# G100_PTC_RS232_201806.net
KiCad netlist of a schematic drawn in Altium Designer
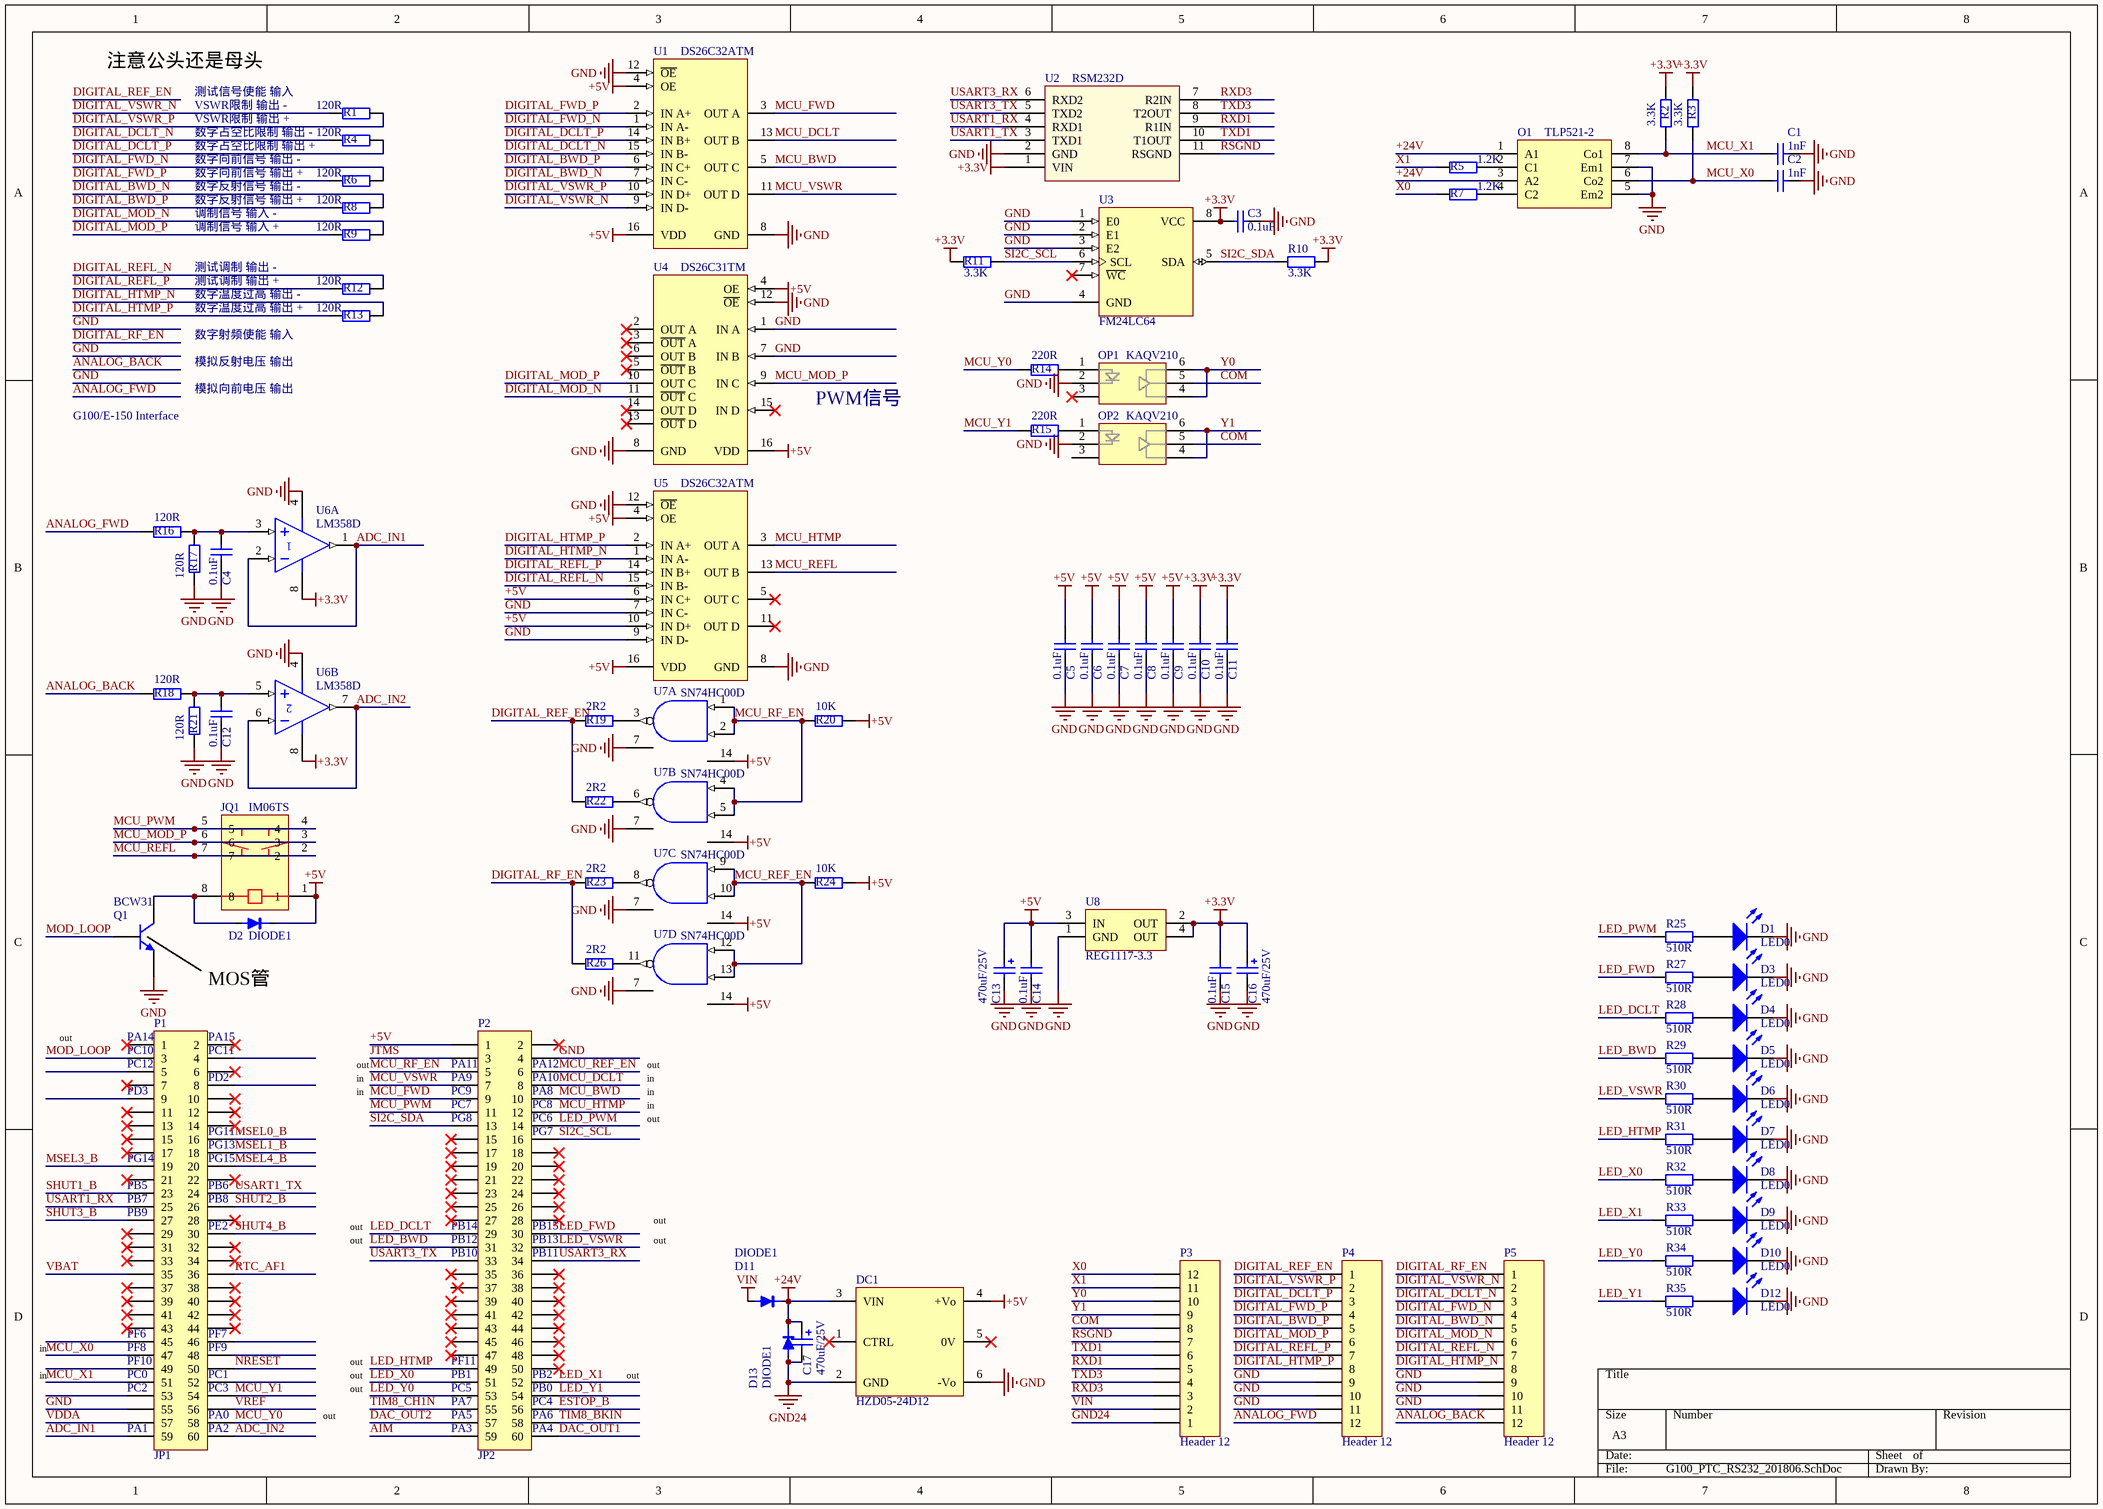
[diagram p0: G100_PTC_RS232_201806.SchDoc]

(export (version "E")
  (design (tool "Eeschema 10.0.6"))
  (components
    (comp (ref "C1")
      (value "1nF")
      (footprint "0805C")
      (description "Capacitor")
      (fields (field (name "PUBLISHER") "Altium Limited"))
      (libsource (lib "Miscellaneous Devices") (part "Cap"))
    )
    (comp (ref "C2")
      (value "1nF")
      (footprint "0805C")
      (description "Capacitor")
      (fields (field (name "PUBLISHER") "Altium Limited"))
      (libsource (lib "Miscellaneous Devices") (part "Cap"))
    )
    (comp (ref "C3")
      (value "0.1uF")
      (footprint "0805C")
      (description "Capacitor")
      (fields (field (name "PUBLISHER") "Altium Limited"))
      (libsource (lib "Miscellaneous Devices") (part "Cap"))
    )
    (comp (ref "C4")
      (value "0.1uF")
      (footprint "0805C")
      (description "Capacitor")
      (fields (field (name "PUBLISHER") "Altium Limited"))
      (libsource (lib "Miscellaneous Devices") (part "Cap"))
    )
    (comp (ref "C5")
      (value "0.1uF")
      (footprint "0805C")
      (description "Capacitor")
      (fields (field (name "PUBLISHER") "Altium Limited"))
      (libsource (lib "Miscellaneous Devices") (part "Cap"))
    )
    (comp (ref "C6")
      (value "0.1uF")
      (footprint "0805C")
      (description "Capacitor")
      (fields (field (name "PUBLISHER") "Altium Limited"))
      (libsource (lib "Miscellaneous Devices") (part "Cap"))
    )
    (comp (ref "C7")
      (value "0.1uF")
      (footprint "0805C")
      (description "Capacitor")
      (fields (field (name "PUBLISHER") "Altium Limited"))
      (libsource (lib "Miscellaneous Devices") (part "Cap"))
    )
    (comp (ref "C8")
      (value "0.1uF")
      (footprint "0805C")
      (description "Capacitor")
      (fields (field (name "PUBLISHER") "Altium Limited"))
      (libsource (lib "Miscellaneous Devices") (part "Cap"))
    )
    (comp (ref "C9")
      (value "0.1uF")
      (footprint "0805C")
      (description "Capacitor")
      (fields (field (name "PUBLISHER") "Altium Limited"))
      (libsource (lib "Miscellaneous Devices") (part "Cap"))
    )
    (comp (ref "C10")
      (value "0.1uF")
      (footprint "0805C")
      (description "Capacitor")
      (fields (field (name "PUBLISHER") "Altium Limited"))
      (libsource (lib "Miscellaneous Devices") (part "Cap"))
    )
    (comp (ref "C11")
      (value "0.1uF")
      (footprint "0805C")
      (description "Capacitor")
      (fields (field (name "PUBLISHER") "Altium Limited"))
      (libsource (lib "Miscellaneous Devices") (part "Cap"))
    )
    (comp (ref "C12")
      (value "0.1uF")
      (footprint "0805C")
      (description "Capacitor")
      (fields (field (name "PUBLISHER") "Altium Limited"))
      (libsource (lib "Miscellaneous Devices") (part "Cap"))
    )
    (comp (ref "C13")
      (value "470uF/25V")
      (footprint "RB3.5-8")
      (description "Polarized Capacitor (Axial)")
      (fields (field (name "PUBLISHER") "Altium Limited"))
      (libsource (lib "Miscellaneous Devices") (part "Cap Pol2"))
    )
    (comp (ref "C14")
      (value "0.1uF")
      (footprint "0805C")
      (description "Capacitor")
      (fields (field (name "PUBLISHER") "Altium Limited"))
      (libsource (lib "Miscellaneous Devices") (part "Cap"))
    )
    (comp (ref "C15")
      (value "0.1uF")
      (footprint "0805C")
      (description "Capacitor")
      (fields (field (name "PUBLISHER") "Altium Limited"))
      (libsource (lib "Miscellaneous Devices") (part "Cap"))
    )
    (comp (ref "C16")
      (value "470uF/25V")
      (footprint "RB3.5-8")
      (description "Polarized Capacitor (Axial)")
      (fields (field (name "PUBLISHER") "Altium Limited"))
      (libsource (lib "Miscellaneous Devices") (part "Cap Pol2"))
    )
    (comp (ref "C17")
      (value "470uF/25V")
      (footprint "RB3.5-8")
      (description "Polarized Capacitor (Axial)")
      (fields (field (name "PUBLISHER") "Altium Limited"))
      (libsource (lib "Miscellaneous Devices") (part "Cap Pol2"))
    )
    (comp (ref "D1")
      (value "LED0")
      (footprint "LEDLight")
      (description "Typical INFRARED GaAs LED")
      (fields (field (name "PUBLISHER") "Altium Limited"))
      (libsource (lib "Miscellaneous Devices") (part "LED0"))
    )
    (comp (ref "D2") (value "DIODE1") (footprint "SOD123") (libsource (lib "常用元件库") (part "DIODE1")))
    (comp (ref "D3")
      (value "LED0")
      (footprint "LEDLight")
      (description "Typical INFRARED GaAs LED")
      (fields (field (name "PUBLISHER") "Altium Limited"))
      (libsource (lib "Miscellaneous Devices") (part "LED0"))
    )
    (comp (ref "D4")
      (value "LED0")
      (footprint "LEDLight")
      (description "Typical INFRARED GaAs LED")
      (fields (field (name "PUBLISHER") "Altium Limited"))
      (libsource (lib "Miscellaneous Devices") (part "LED0"))
    )
    (comp (ref "D5")
      (value "LED0")
      (footprint "LEDLight")
      (description "Typical INFRARED GaAs LED")
      (fields (field (name "PUBLISHER") "Altium Limited"))
      (libsource (lib "Miscellaneous Devices") (part "LED0"))
    )
    (comp (ref "D6")
      (value "LED0")
      (footprint "LEDLight")
      (description "Typical INFRARED GaAs LED")
      (fields (field (name "PUBLISHER") "Altium Limited"))
      (libsource (lib "Miscellaneous Devices") (part "LED0"))
    )
    (comp (ref "D7")
      (value "LED0")
      (footprint "LEDLight")
      (description "Typical INFRARED GaAs LED")
      (fields (field (name "PUBLISHER") "Altium Limited"))
      (libsource (lib "Miscellaneous Devices") (part "LED0"))
    )
    (comp (ref "D8")
      (value "LED0")
      (footprint "LEDLight")
      (description "Typical INFRARED GaAs LED")
      (fields (field (name "PUBLISHER") "Altium Limited"))
      (libsource (lib "Miscellaneous Devices") (part "LED0"))
    )
    (comp (ref "D9")
      (value "LED0")
      (footprint "LEDLight")
      (description "Typical INFRARED GaAs LED")
      (fields (field (name "PUBLISHER") "Altium Limited"))
      (libsource (lib "Miscellaneous Devices") (part "LED0"))
    )
    (comp (ref "D10")
      (value "LED0")
      (footprint "LEDLight")
      (description "Typical INFRARED GaAs LED")
      (fields (field (name "PUBLISHER") "Altium Limited"))
      (libsource (lib "Miscellaneous Devices") (part "LED0"))
    )
    (comp (ref "D11") (value "DIODE1") (footprint "DIODE-DO56") (libsource (lib "常用元件库") (part "DIODE1")))
    (comp (ref "D12")
      (value "LED0")
      (footprint "LEDLight")
      (description "Typical INFRARED GaAs LED")
      (fields (field (name "PUBLISHER") "Altium Limited"))
      (libsource (lib "Miscellaneous Devices") (part "LED0"))
    )
    (comp (ref "D13") (value "DIODE1") (footprint "DIODE-DO56") (libsource (lib "常用元件库") (part "DIODE1")))
    (comp (ref "DC1")
      (value "HZD05-24D12")
      (footprint "HZ03V2")
      (libsource (lib "常用原理图库") (part "HZD05-24D12"))
    )
    (comp (ref "JQ1") (value "IM06TS") (footprint "IM06TS") (libsource (lib "常用原理图库") (part "IM06TS")))
    (comp (ref "O1")
      (value "TLP521-2")
      (footprint "DIP-8")
      (description "Photocoupler")
      (libsource (lib "常用原理图库") (part "TLP521-2"))
    )
    (comp (ref "OP1") (value "KAQV210") (footprint "DIP-6") (libsource (lib "常用原理图库") (part "KAQV210")))
    (comp (ref "OP2") (value "KAQV210") (footprint "DIP-6") (libsource (lib "常用原理图库") (part "KAQV210")))
    (comp (ref "P1")
      (value "JP1")
      (footprint "HDR2X30")
      (description "Header, 30-Pin, Dual row")
      (fields (field (name "PUBLISHER") "Altium Limited"))
      (libsource (lib "Miscellaneous Connectors") (part "Header 30X2"))
    )
    (comp (ref "P2")
      (value "JP2")
      (footprint "HDR2X30")
      (description "Header, 30-Pin, Dual row")
      (fields (field (name "PUBLISHER") "Altium Limited"))
      (libsource (lib "Miscellaneous Connectors") (part "Header 30X2"))
    )
    (comp (ref "P3")
      (value "Header 12")
      (footprint "15EDGVM-3.5-12P-14")
      (description "Header, 12-Pin")
      (fields (field (name "PUBLISHER") "Altium Limited"))
      (libsource (lib "") (part "Header 12_1"))
    )
    (comp (ref "P4")
      (value "Header 12")
      (footprint "15EDGVM-3.5-12P-14")
      (description "Header, 12-Pin")
      (fields (field (name "PUBLISHER") "Altium Limited"))
      (libsource (lib "Miscellaneous Connectors") (part "Header 12"))
    )
    (comp (ref "P5")
      (value "Header 12")
      (footprint "15EDGVM-3.5-12P-14")
      (description "Header, 12-Pin")
      (fields (field (name "PUBLISHER") "Altium Limited"))
      (libsource (lib "Miscellaneous Connectors") (part "Header 12"))
    )
    (comp (ref "Q1")
      (value "BCW31")
      (footprint "SOT-23A")
      (description "NPN Epitaxial Silicon Transistor")
      (fields (field (name "PUBLISHER") "Altium Limited"))
      (libsource (lib "FSC Discrete BJT") (part "BCW31"))
    )
    (comp (ref "R1")
      (value "120R")
      (footprint "0805C")
      (description "Resistor")
      (fields (field (name "PUBLISHER") "Altium Limited"))
      (libsource (lib "Miscellaneous Devices") (part "Res2"))
    )
    (comp (ref "R2")
      (value "3.3K")
      (footprint "0805C")
      (description "Resistor")
      (fields (field (name "PUBLISHER") "Altium Limited"))
      (libsource (lib "") (part "Res2_3"))
    )
    (comp (ref "R3")
      (value "3.3K")
      (footprint "0805C")
      (description "Resistor")
      (fields (field (name "PUBLISHER") "Altium Limited"))
      (libsource (lib "") (part "Res2_3"))
    )
    (comp (ref "R4")
      (value "120R")
      (footprint "0805C")
      (description "Resistor")
      (fields (field (name "PUBLISHER") "Altium Limited"))
      (libsource (lib "Miscellaneous Devices") (part "Res2"))
    )
    (comp (ref "R5")
      (value "1.2K")
      (footprint "6332[2512]")
      (description "Resistor")
      (fields (field (name "PUBLISHER") "Altium Limited"))
      (libsource (lib "") (part "Res2_1"))
    )
    (comp (ref "R6")
      (value "120R")
      (footprint "0805C")
      (description "Resistor")
      (fields (field (name "PUBLISHER") "Altium Limited"))
      (libsource (lib "Miscellaneous Devices") (part "Res2"))
    )
    (comp (ref "R7")
      (value "1.2K")
      (footprint "6332[2512]")
      (description "Resistor")
      (fields (field (name "PUBLISHER") "Altium Limited"))
      (libsource (lib "") (part "Res2_1"))
    )
    (comp (ref "R8")
      (value "120R")
      (footprint "0805C")
      (description "Resistor")
      (fields (field (name "PUBLISHER") "Altium Limited"))
      (libsource (lib "Miscellaneous Devices") (part "Res2"))
    )
    (comp (ref "R9")
      (value "120R")
      (footprint "0805C")
      (description "Resistor")
      (fields (field (name "PUBLISHER") "Altium Limited"))
      (libsource (lib "Miscellaneous Devices") (part "Res2"))
    )
    (comp (ref "R10")
      (value "3.3K")
      (footprint "0805C")
      (description "Resistor")
      (fields (field (name "PUBLISHER") "Altium Limited"))
      (libsource (lib "") (part "Res2_1"))
    )
    (comp (ref "R11")
      (value "3.3K")
      (footprint "0805C")
      (description "Resistor")
      (fields (field (name "PUBLISHER") "Altium Limited"))
      (libsource (lib "Miscellaneous Devices") (part "Res2"))
    )
    (comp (ref "R12")
      (value "120R")
      (footprint "0805C")
      (description "Resistor")
      (fields (field (name "PUBLISHER") "Altium Limited"))
      (libsource (lib "Miscellaneous Devices") (part "Res2"))
    )
    (comp (ref "R13")
      (value "120R")
      (footprint "0805C")
      (description "Resistor")
      (fields (field (name "PUBLISHER") "Altium Limited"))
      (libsource (lib "Miscellaneous Devices") (part "Res2"))
    )
    (comp (ref "R14")
      (value "220R")
      (footprint "0805C")
      (description "Resistor")
      (fields (field (name "PUBLISHER") "Altium Limited"))
      (libsource (lib "Miscellaneous Devices") (part "Res2"))
    )
    (comp (ref "R15")
      (value "220R")
      (footprint "0805C")
      (description "Resistor")
      (fields (field (name "PUBLISHER") "Altium Limited"))
      (libsource (lib "Miscellaneous Devices") (part "Res2"))
    )
    (comp (ref "R16")
      (value "120R")
      (footprint "0805C")
      (description "Resistor")
      (fields (field (name "PUBLISHER") "Altium Limited"))
      (libsource (lib "Miscellaneous Devices") (part "Res2"))
    )
    (comp (ref "R17")
      (value "120R")
      (footprint "0805C")
      (description "Resistor")
      (fields (field (name "PUBLISHER") "Altium Limited"))
      (libsource (lib "") (part "Res2_2"))
    )
    (comp (ref "R18")
      (value "120R")
      (footprint "0805C")
      (description "Resistor")
      (fields (field (name "PUBLISHER") "Altium Limited"))
      (libsource (lib "Miscellaneous Devices") (part "Res2"))
    )
    (comp (ref "R19")
      (value "2R2")
      (footprint "0805C")
      (description "Resistor")
      (fields (field (name "PUBLISHER") "Altium Limited"))
      (libsource (lib "Miscellaneous Devices") (part "Res2"))
    )
    (comp (ref "R20")
      (value "10K")
      (footprint "0805C")
      (description "Resistor")
      (fields (field (name "PUBLISHER") "Altium Limited"))
      (libsource (lib "Miscellaneous Devices") (part "Res2"))
    )
    (comp (ref "R21")
      (value "120R")
      (footprint "0805C")
      (description "Resistor")
      (fields (field (name "PUBLISHER") "Altium Limited"))
      (libsource (lib "") (part "Res2_2"))
    )
    (comp (ref "R22")
      (value "2R2")
      (footprint "0805C")
      (description "Resistor")
      (fields (field (name "PUBLISHER") "Altium Limited"))
      (libsource (lib "Miscellaneous Devices") (part "Res2"))
    )
    (comp (ref "R23")
      (value "2R2")
      (footprint "0805C")
      (description "Resistor")
      (fields (field (name "PUBLISHER") "Altium Limited"))
      (libsource (lib "Miscellaneous Devices") (part "Res2"))
    )
    (comp (ref "R24")
      (value "10K")
      (footprint "0805C")
      (description "Resistor")
      (fields (field (name "PUBLISHER") "Altium Limited"))
      (libsource (lib "Miscellaneous Devices") (part "Res2"))
    )
    (comp (ref "R25")
      (value "510R")
      (footprint "0805C")
      (description "Resistor")
      (fields (field (name "PUBLISHER") "Altium Limited"))
      (libsource (lib "") (part "Res2_1"))
    )
    (comp (ref "R26")
      (value "2R2")
      (footprint "0805C")
      (description "Resistor")
      (fields (field (name "PUBLISHER") "Altium Limited"))
      (libsource (lib "Miscellaneous Devices") (part "Res2"))
    )
    (comp (ref "R27")
      (value "510R")
      (footprint "0805C")
      (description "Resistor")
      (fields (field (name "PUBLISHER") "Altium Limited"))
      (libsource (lib "") (part "Res2_1"))
    )
    (comp (ref "R28")
      (value "510R")
      (footprint "0805C")
      (description "Resistor")
      (fields (field (name "PUBLISHER") "Altium Limited"))
      (libsource (lib "") (part "Res2_1"))
    )
    (comp (ref "R29")
      (value "510R")
      (footprint "0805C")
      (description "Resistor")
      (fields (field (name "PUBLISHER") "Altium Limited"))
      (libsource (lib "") (part "Res2_1"))
    )
    (comp (ref "R30")
      (value "510R")
      (footprint "0805C")
      (description "Resistor")
      (fields (field (name "PUBLISHER") "Altium Limited"))
      (libsource (lib "") (part "Res2_1"))
    )
    (comp (ref "R31")
      (value "510R")
      (footprint "0805C")
      (description "Resistor")
      (fields (field (name "PUBLISHER") "Altium Limited"))
      (libsource (lib "") (part "Res2_1"))
    )
    (comp (ref "R32")
      (value "510R")
      (footprint "0805C")
      (description "Resistor")
      (fields (field (name "PUBLISHER") "Altium Limited"))
      (libsource (lib "") (part "Res2_1"))
    )
    (comp (ref "R33")
      (value "510R")
      (footprint "0805C")
      (description "Resistor")
      (fields (field (name "PUBLISHER") "Altium Limited"))
      (libsource (lib "") (part "Res2_1"))
    )
    (comp (ref "R34")
      (value "510R")
      (footprint "0805C")
      (description "Resistor")
      (fields (field (name "PUBLISHER") "Altium Limited"))
      (libsource (lib "") (part "Res2_1"))
    )
    (comp (ref "R35")
      (value "510R")
      (footprint "0805C")
      (description "Resistor")
      (fields (field (name "PUBLISHER") "Altium Limited"))
      (libsource (lib "") (part "Res2_1"))
    )
    (comp (ref "U1")
      (value "DS26C32ATM")
      (footprint "M16A_L")
      (description "CMOS Quad Differential Line Receiver")
      (fields
        (field (name "MANUFACTURER") "National Semiconductor")
        (field (name "DIGIKEYPARTNUMBER") "DS26C32ATM-ND")
        (field (name "PUBLISHER") "Altium Limited")
      )
      (libsource (lib "NSC Interface") (part "DS26C32ATM"))
    )
    (comp (ref "U2")
      (value "RSM232D")
      (footprint "CTM-8251D")
      (description "双路隔离RS-232收发器")
      (libsource (lib "常用原理图库") (part "RSM232D"))
    )
    (comp (ref "U3")
      (value "FM24LC64")
      (footprint "SOP8_L")
      (description "64 Kbit Serial I²C Bus EEPROM")
      (fields (field (name "PUBLISHER") "Altium Limited"))
      (libsource (lib "ST Memory EEPROM Serial") (part "M24C64MN3"))
    )
    (comp (ref "U4")
      (value "DS26C31TM")
      (footprint "M16A_L")
      (description "CMOS Quad Tri-State Differential Line Driver")
      (fields
        (field (name "MANUFACTURER") "National Semiconductor")
        (field (name "DIGIKEYPARTNUMBER") "DS26C31TM-ND")
        (field (name "PUBLISHER") "Altium Limited")
      )
      (libsource (lib "NSC Interface") (part "DS26C31TM"))
    )
    (comp (ref "U5")
      (value "DS26C32ATM")
      (footprint "M16A_L")
      (description "CMOS Quad Differential Line Receiver")
      (fields
        (field (name "MANUFACTURER") "National Semiconductor")
        (field (name "DIGIKEYPARTNUMBER") "DS26C32ATM-ND")
        (field (name "PUBLISHER") "Altium Limited")
      )
      (libsource (lib "NSC Interface") (part "DS26C32ATM"))
    )
    (comp (ref "U6")
      (value "LM358D")
      (footprint "751-02_N")
      (description "Dual Low-Power Operational Amplifier")
      (fields (field (name "PUBLISHER") "Altium Limited"))
      (libsource (lib "Motorola Amplifier Operational Amplifier") (part "LM358D"))
    )
    (comp (ref "U7")
      (value "SN74HC00D")
      (footprint "D014_N")
      (description "Quadruple 2-Input Positive-NAND Gate")
      (fields (field (name "PUBLISHER") "Altium Limited"))
      (libsource (lib "TI Logic Gate 2") (part "SN74HC00D"))
    )
    (comp (ref "U8")
      (value "REG1117-3.3")
      (footprint "ZZ311")
      (description "800mA and 1A Low Dropout Positive Regulator 2.85V, 3.3V, 5V, and Adjustable")
      (fields (field (name "PUBLISHER") "Altium Limited"))
      (libsource (lib "BB Power Mgt Voltage Regulator") (part "REG1117-3.3"))
    )
  )
  (nets
    (net (code "1") (name "+3.3V") (class "Default")
      (node (ref "C10") (pin "2") (pinfunction "2_2") (pintype "passive"))
      (node (ref "C11") (pin "2") (pinfunction "2_2") (pintype "passive"))
      (node (ref "C15") (pin "2") (pinfunction "2_2") (pintype "passive"))
      (node (ref "C16") (pin "1") (pinfunction "1_1") (pintype "passive"))
      (node (ref "C3") (pin "2") (pinfunction "2_2") (pintype "passive"))
      (node (ref "R10") (pin "2") (pinfunction "2_2") (pintype "passive"))
      (node (ref "R11") (pin "2") (pinfunction "2_2") (pintype "passive"))
      (node (ref "R2") (pin "2") (pinfunction "2_2") (pintype "passive"))
      (node (ref "R3") (pin "2") (pinfunction "2_2") (pintype "passive"))
      (node (ref "U2") (pin "1") (pinfunction "VIN_1") (pintype "passive"))
      (node (ref "U3") (pin "8") (pinfunction "VCC_8") (pintype "power_in"))
      (node (ref "U6") (pin "8") (pinfunction "V+_8") (pintype "power_in"))
      (node (ref "U8") (pin "2") (pinfunction "OUT_2") (pintype "power_in"))
      (node (ref "U8") (pin "4") (pinfunction "OUT_4") (pintype "power_in"))
    )
    (net (code "2") (name "+5V") (class "Default")
      (node (ref "C13") (pin "1") (pinfunction "1_1") (pintype "passive"))
      (node (ref "C14") (pin "2") (pinfunction "2_2") (pintype "passive"))
      (node (ref "C5") (pin "2") (pinfunction "2_2") (pintype "passive"))
      (node (ref "C6") (pin "2") (pinfunction "2_2") (pintype "passive"))
      (node (ref "C7") (pin "2") (pinfunction "2_2") (pintype "passive"))
      (node (ref "C8") (pin "2") (pinfunction "2_2") (pintype "passive"))
      (node (ref "C9") (pin "2") (pinfunction "2_2") (pintype "passive"))
      (node (ref "D2") (pin "2") (pinfunction "K_2") (pintype "passive"))
      (node (ref "DC1") (pin "4") (pinfunction "+Vo_4") (pintype "passive"))
      (node (ref "JQ1") (pin "1") (pinfunction "1_1") (pintype "passive"))
      (node (ref "P2") (pin "1") (pinfunction "1_1") (pintype "passive"))
      (node (ref "R20") (pin "1") (pinfunction "1_1") (pintype "passive"))
      (node (ref "R24") (pin "1") (pinfunction "1_1") (pintype "passive"))
      (node (ref "U1") (pin "16") (pinfunction "VDD_16") (pintype "power_in"))
      (node (ref "U1") (pin "4") (pinfunction "OE_4") (pintype "input"))
      (node (ref "U4") (pin "16") (pinfunction "VDD_16") (pintype "power_in"))
      (node (ref "U4") (pin "4") (pinfunction "OE_4") (pintype "input"))
      (node (ref "U5") (pin "10") (pinfunction "IN_D+_10") (pintype "input"))
      (node (ref "U5") (pin "16") (pinfunction "VDD_16") (pintype "power_in"))
      (node (ref "U5") (pin "4") (pinfunction "OE_4") (pintype "input"))
      (node (ref "U5") (pin "6") (pinfunction "IN_C+_6") (pintype "input"))
      (node (ref "U7") (pin "14") (pinfunction "VCC_14") (pintype "power_in"))
      (node (ref "U8") (pin "3") (pinfunction "IN_3") (pintype "power_in"))
    )
    (net (code "3") (name "+24V") (class "Default")
      (node (ref "C17") (pin "1") (pinfunction "1_1") (pintype "passive"))
      (node (ref "D11") (pin "2") (pinfunction "K_2") (pintype "passive"))
      (node (ref "D13") (pin "2") (pinfunction "K_2") (pintype "passive"))
      (node (ref "DC1") (pin "3") (pinfunction "VIN_3") (pintype "passive"))
      (node (ref "O1") (pin "1") (pinfunction "A1_1") (pintype "passive"))
      (node (ref "O1") (pin "3") (pinfunction "A2_3") (pintype "passive"))
    )
    (net (code "4") (name "/ADC_IN1") (class "Default")
      (node (ref "P1") (pin "59") (pinfunction "59_59") (pintype "passive"))
      (node (ref "U6") (pin "1") (pinfunction "OUT_1") (pintype "output"))
      (node (ref "U6") (pin "2") (pinfunction "IN-_2") (pintype "input"))
    )
    (net (code "5") (name "/ADC_IN2") (class "Default")
      (node (ref "P1") (pin "60") (pinfunction "60_60") (pintype "passive"))
      (node (ref "U6") (pin "6") (pinfunction "IN-_6") (pintype "input"))
      (node (ref "U6") (pin "7") (pinfunction "OUT_7") (pintype "output"))
    )
    (net (code "6") (name "/AIM") (class "Default")
      (node (ref "P2") (pin "59") (pinfunction "59_59") (pintype "passive"))
    )
    (net (code "7") (name "/ANALOG_BACK") (class "Default")
      (node (ref "P5") (pin "12") (pinfunction "12_12") (pintype "passive"))
      (node (ref "R18") (pin "2") (pinfunction "2_2") (pintype "passive"))
    )
    (net (code "8") (name "/ANALOG_FWD") (class "Default")
      (node (ref "P4") (pin "12") (pinfunction "12_12") (pintype "passive"))
      (node (ref "R16") (pin "2") (pinfunction "2_2") (pintype "passive"))
    )
    (net (code "9") (name "/COM") (class "Default")
      (node (ref "OP1") (pin "5") (pinfunction "5_5") (pintype "passive"))
      (node (ref "OP2") (pin "5") (pinfunction "5_5") (pintype "passive"))
      (node (ref "P3") (pin "8") (pinfunction "8_8") (pintype "passive"))
    )
    (net (code "10") (name "/DAC_OUT1") (class "Default")
      (node (ref "P2") (pin "60") (pinfunction "60_60") (pintype "passive"))
    )
    (net (code "11") (name "/DAC_OUT2") (class "Default")
      (node (ref "P2") (pin "57") (pinfunction "57_57") (pintype "passive"))
    )
    (net (code "12") (name "/DIGITAL_BWD_N") (class "Default")
      (node (ref "P5") (pin "5") (pinfunction "5_5") (pintype "passive"))
      (node (ref "R8") (pin "1") (pinfunction "1_1") (pintype "passive"))
      (node (ref "U1") (pin "7") (pinfunction "IN_C-_7") (pintype "input"))
    )
    (net (code "13") (name "/DIGITAL_BWD_P") (class "Default")
      (node (ref "P4") (pin "5") (pinfunction "5_5") (pintype "passive"))
      (node (ref "R8") (pin "2") (pinfunction "2_2") (pintype "passive"))
      (node (ref "U1") (pin "6") (pinfunction "IN_C+_6") (pintype "input"))
    )
    (net (code "14") (name "/DIGITAL_DCLT_N") (class "Default")
      (node (ref "P5") (pin "3") (pinfunction "3_3") (pintype "passive"))
      (node (ref "R4") (pin "2") (pinfunction "2_2") (pintype "passive"))
      (node (ref "U1") (pin "15") (pinfunction "IN_B-_15") (pintype "input"))
    )
    (net (code "15") (name "/DIGITAL_DCLT_P") (class "Default")
      (node (ref "P4") (pin "3") (pinfunction "3_3") (pintype "passive"))
      (node (ref "R4") (pin "1") (pinfunction "1_1") (pintype "passive"))
      (node (ref "U1") (pin "14") (pinfunction "IN_B+_14") (pintype "input"))
    )
    (net (code "16") (name "/DIGITAL_FWD_N") (class "Default")
      (node (ref "P5") (pin "4") (pinfunction "4_4") (pintype "passive"))
      (node (ref "R6") (pin "1") (pinfunction "1_1") (pintype "passive"))
      (node (ref "U1") (pin "1") (pinfunction "IN_A-_1") (pintype "input"))
    )
    (net (code "17") (name "/DIGITAL_FWD_P") (class "Default")
      (node (ref "P4") (pin "4") (pinfunction "4_4") (pintype "passive"))
      (node (ref "R6") (pin "2") (pinfunction "2_2") (pintype "passive"))
      (node (ref "U1") (pin "2") (pinfunction "IN_A+_2") (pintype "input"))
    )
    (net (code "18") (name "/DIGITAL_HTMP_N") (class "Default")
      (node (ref "P5") (pin "8") (pinfunction "8_8") (pintype "passive"))
      (node (ref "R13") (pin "1") (pinfunction "1_1") (pintype "passive"))
      (node (ref "U5") (pin "1") (pinfunction "IN_A-_1") (pintype "input"))
    )
    (net (code "19") (name "/DIGITAL_HTMP_P") (class "Default")
      (node (ref "P4") (pin "8") (pinfunction "8_8") (pintype "passive"))
      (node (ref "R13") (pin "2") (pinfunction "2_2") (pintype "passive"))
      (node (ref "U5") (pin "2") (pinfunction "IN_A+_2") (pintype "input"))
    )
    (net (code "20") (name "/DIGITAL_MOD_N") (class "Default")
      (node (ref "P5") (pin "6") (pinfunction "6_6") (pintype "passive"))
      (node (ref "R9") (pin "1") (pinfunction "1_1") (pintype "passive"))
      (node (ref "U4") (pin "11") (pinfunction "~{OUT}_C_11") (pintype "tri_state"))
    )
    (net (code "21") (name "/DIGITAL_MOD_P") (class "Default")
      (node (ref "P4") (pin "6") (pinfunction "6_6") (pintype "passive"))
      (node (ref "R9") (pin "2") (pinfunction "2_2") (pintype "passive"))
      (node (ref "U4") (pin "10") (pinfunction "OUT_C_10") (pintype "tri_state"))
    )
    (net (code "22") (name "/DIGITAL_REFL_N") (class "Default")
      (node (ref "P5") (pin "7") (pinfunction "7_7") (pintype "passive"))
      (node (ref "R12") (pin "1") (pinfunction "1_1") (pintype "passive"))
      (node (ref "U5") (pin "15") (pinfunction "IN_B-_15") (pintype "input"))
    )
    (net (code "23") (name "/DIGITAL_REFL_P") (class "Default")
      (node (ref "P4") (pin "7") (pinfunction "7_7") (pintype "passive"))
      (node (ref "R12") (pin "2") (pinfunction "2_2") (pintype "passive"))
      (node (ref "U5") (pin "14") (pinfunction "IN_B+_14") (pintype "input"))
    )
    (net (code "24") (name "/DIGITAL_REF_EN") (class "Default")
      (node (ref "P4") (pin "1") (pinfunction "1_1") (pintype "passive"))
      (node (ref "R19") (pin "2") (pinfunction "2_2") (pintype "passive"))
      (node (ref "R22") (pin "2") (pinfunction "2_2") (pintype "passive"))
    )
    (net (code "25") (name "/DIGITAL_RF_EN") (class "Default")
      (node (ref "P5") (pin "1") (pinfunction "1_1") (pintype "passive"))
      (node (ref "R23") (pin "2") (pinfunction "2_2") (pintype "passive"))
      (node (ref "R26") (pin "2") (pinfunction "2_2") (pintype "passive"))
    )
    (net (code "26") (name "/DIGITAL_VSWR_N") (class "Default")
      (node (ref "P5") (pin "2") (pinfunction "2_2") (pintype "passive"))
      (node (ref "R1") (pin "2") (pinfunction "2_2") (pintype "passive"))
      (node (ref "U1") (pin "9") (pinfunction "IN_D-_9") (pintype "input"))
    )
    (net (code "27") (name "/DIGITAL_VSWR_P") (class "Default")
      (node (ref "P4") (pin "2") (pinfunction "2_2") (pintype "passive"))
      (node (ref "R1") (pin "1") (pinfunction "1_1") (pintype "passive"))
      (node (ref "U1") (pin "10") (pinfunction "IN_D+_10") (pintype "input"))
    )
    (net (code "28") (name "/ESTOP_B") (class "Default")
      (node (ref "P2") (pin "56") (pinfunction "56_56") (pintype "passive"))
    )
    (net (code "29") (name "/JTMS") (class "Default")
      (node (ref "P2") (pin "3") (pinfunction "3_3") (pintype "passive"))
    )
    (net (code "30") (name "/LED_BWD") (class "Default")
      (node (ref "P2") (pin "31") (pinfunction "31_31") (pintype "passive"))
      (node (ref "R29") (pin "1") (pinfunction "1_1") (pintype "passive"))
    )
    (net (code "31") (name "/LED_DCLT") (class "Default")
      (node (ref "P2") (pin "29") (pinfunction "29_29") (pintype "passive"))
      (node (ref "R28") (pin "1") (pinfunction "1_1") (pintype "passive"))
    )
    (net (code "32") (name "/LED_FWD") (class "Default")
      (node (ref "P2") (pin "30") (pinfunction "30_30") (pintype "passive"))
      (node (ref "R27") (pin "1") (pinfunction "1_1") (pintype "passive"))
    )
    (net (code "33") (name "/LED_HTMP") (class "Default")
      (node (ref "P2") (pin "49") (pinfunction "49_49") (pintype "passive"))
      (node (ref "R31") (pin "1") (pinfunction "1_1") (pintype "passive"))
    )
    (net (code "34") (name "/LED_PWM") (class "Default")
      (node (ref "P2") (pin "14") (pinfunction "14_14") (pintype "passive"))
      (node (ref "R25") (pin "1") (pinfunction "1_1") (pintype "passive"))
    )
    (net (code "35") (name "/LED_VSWR") (class "Default")
      (node (ref "P2") (pin "32") (pinfunction "32_32") (pintype "passive"))
      (node (ref "R30") (pin "1") (pinfunction "1_1") (pintype "passive"))
    )
    (net (code "36") (name "/LED_X0") (class "Default")
      (node (ref "P2") (pin "51") (pinfunction "51_51") (pintype "passive"))
      (node (ref "R32") (pin "1") (pinfunction "1_1") (pintype "passive"))
    )
    (net (code "37") (name "/LED_X1") (class "Default")
      (node (ref "P2") (pin "52") (pinfunction "52_52") (pintype "passive"))
      (node (ref "R33") (pin "1") (pinfunction "1_1") (pintype "passive"))
    )
    (net (code "38") (name "/LED_Y0") (class "Default")
      (node (ref "P2") (pin "53") (pinfunction "53_53") (pintype "passive"))
      (node (ref "R34") (pin "1") (pinfunction "1_1") (pintype "passive"))
    )
    (net (code "39") (name "/LED_Y1") (class "Default")
      (node (ref "P2") (pin "54") (pinfunction "54_54") (pintype "passive"))
      (node (ref "R35") (pin "1") (pinfunction "1_1") (pintype "passive"))
    )
    (net (code "40") (name "/MCU_BWD") (class "Default")
      (node (ref "P2") (pin "10") (pinfunction "10_10") (pintype "passive"))
      (node (ref "U1") (pin "5") (pinfunction "OUT_C_5") (pintype "tri_state"))
    )
    (net (code "41") (name "/MCU_DCLT") (class "Default")
      (node (ref "P2") (pin "8") (pinfunction "8_8") (pintype "passive"))
      (node (ref "U1") (pin "13") (pinfunction "OUT_B_13") (pintype "tri_state"))
    )
    (net (code "42") (name "/MCU_FWD") (class "Default")
      (node (ref "P2") (pin "9") (pinfunction "9_9") (pintype "passive"))
      (node (ref "U1") (pin "3") (pinfunction "OUT_A_3") (pintype "tri_state"))
    )
    (net (code "43") (name "/MCU_HTMP") (class "Default")
      (node (ref "P2") (pin "12") (pinfunction "12_12") (pintype "passive"))
      (node (ref "U5") (pin "3") (pinfunction "OUT_A_3") (pintype "tri_state"))
    )
    (net (code "44") (name "/MCU_MOD_P") (class "Default")
      (node (ref "JQ1") (pin "3") (pinfunction "3_3") (pintype "passive"))
      (node (ref "JQ1") (pin "6") (pinfunction "6_6") (pintype "passive"))
      (node (ref "U4") (pin "9") (pinfunction "IN_C_9") (pintype "input"))
    )
    (net (code "45") (name "/MCU_PWM") (class "Default")
      (node (ref "JQ1") (pin "4") (pinfunction "4_4") (pintype "passive"))
      (node (ref "JQ1") (pin "5") (pinfunction "5_5") (pintype "passive"))
      (node (ref "P2") (pin "11") (pinfunction "11_11") (pintype "passive"))
    )
    (net (code "46") (name "/MCU_REFL") (class "Default")
      (node (ref "JQ1") (pin "2") (pinfunction "2_2") (pintype "passive"))
      (node (ref "JQ1") (pin "7") (pinfunction "7_7") (pintype "passive"))
      (node (ref "U5") (pin "13") (pinfunction "OUT_B_13") (pintype "tri_state"))
    )
    (net (code "47") (name "/MCU_REF_EN") (class "Default")
      (node (ref "P2") (pin "6") (pinfunction "6_6") (pintype "passive"))
      (node (ref "R24") (pin "2") (pinfunction "2_2") (pintype "passive"))
      (node (ref "U7") (pin "10") (pinfunction "B_10") (pintype "input"))
      (node (ref "U7") (pin "12") (pinfunction "A_12") (pintype "input"))
      (node (ref "U7") (pin "13") (pinfunction "B_13") (pintype "input"))
      (node (ref "U7") (pin "9") (pinfunction "A_9") (pintype "input"))
    )
    (net (code "48") (name "/MCU_RF_EN") (class "Default")
      (node (ref "P2") (pin "5") (pinfunction "5_5") (pintype "passive"))
      (node (ref "R20") (pin "2") (pinfunction "2_2") (pintype "passive"))
      (node (ref "U7") (pin "1") (pinfunction "A_1") (pintype "input"))
      (node (ref "U7") (pin "2") (pinfunction "B_2") (pintype "input"))
      (node (ref "U7") (pin "4") (pinfunction "A_4") (pintype "input"))
      (node (ref "U7") (pin "5") (pinfunction "B_5") (pintype "input"))
    )
    (net (code "49") (name "/MCU_VSWR") (class "Default")
      (node (ref "P2") (pin "7") (pinfunction "7_7") (pintype "passive"))
      (node (ref "U1") (pin "11") (pinfunction "OUT_D_11") (pintype "tri_state"))
    )
    (net (code "50") (name "/MCU_X0") (class "Default")
      (node (ref "C2") (pin "1") (pinfunction "1_1") (pintype "passive"))
      (node (ref "O1") (pin "6") (pinfunction "Co2_6") (pintype "passive"))
      (node (ref "P1") (pin "47") (pinfunction "47_47") (pintype "passive"))
      (node (ref "R3") (pin "1") (pinfunction "1_1") (pintype "passive"))
    )
    (net (code "51") (name "/MCU_X1") (class "Default")
      (node (ref "C1") (pin "1") (pinfunction "1_1") (pintype "passive"))
      (node (ref "O1") (pin "8") (pinfunction "Co1_8") (pintype "passive"))
      (node (ref "P1") (pin "51") (pinfunction "51_51") (pintype "passive"))
      (node (ref "R2") (pin "1") (pinfunction "1_1") (pintype "passive"))
    )
    (net (code "52") (name "/MCU_Y0") (class "Default")
      (node (ref "P1") (pin "58") (pinfunction "58_58") (pintype "passive"))
      (node (ref "R14") (pin "2") (pinfunction "2_2") (pintype "passive"))
    )
    (net (code "53") (name "/MCU_Y1") (class "Default")
      (node (ref "P1") (pin "54") (pinfunction "54_54") (pintype "passive"))
      (node (ref "R15") (pin "2") (pinfunction "2_2") (pintype "passive"))
    )
    (net (code "54") (name "/MOD_LOOP") (class "Default")
      (node (ref "P1") (pin "3") (pinfunction "3_3") (pintype "passive"))
      (node (ref "Q1") (pin "1") (pinfunction "B_1") (pintype "passive"))
    )
    (net (code "55") (name "/MSEL0_B") (class "Default")
      (node (ref "P1") (pin "16") (pinfunction "16_16") (pintype "passive"))
    )
    (net (code "56") (name "/MSEL1_B") (class "Default")
      (node (ref "P1") (pin "18") (pinfunction "18_18") (pintype "passive"))
    )
    (net (code "57") (name "/MSEL3_B") (class "Default")
      (node (ref "P1") (pin "19") (pinfunction "19_19") (pintype "passive"))
    )
    (net (code "58") (name "/MSEL4_B") (class "Default")
      (node (ref "P1") (pin "20") (pinfunction "20_20") (pintype "passive"))
    )
    (net (code "59") (name "/NRESET") (class "Default")
      (node (ref "P1") (pin "50") (pinfunction "50_50") (pintype "passive"))
    )
    (net (code "60") (name "/RSGND") (class "Default")
      (node (ref "P3") (pin "7") (pinfunction "7_7") (pintype "passive"))
      (node (ref "U2") (pin "11") (pinfunction "RSGND_11") (pintype "passive"))
    )
    (net (code "61") (name "/RTC_AF1") (class "Default")
      (node (ref "P1") (pin "36") (pinfunction "36_36") (pintype "passive"))
    )
    (net (code "62") (name "/RXD1") (class "Default")
      (node (ref "P3") (pin "5") (pinfunction "5_5") (pintype "passive"))
      (node (ref "U2") (pin "9") (pinfunction "R1IN_9") (pintype "passive"))
    )
    (net (code "63") (name "/RXD3") (class "Default")
      (node (ref "P3") (pin "3") (pinfunction "3_3") (pintype "passive"))
      (node (ref "U2") (pin "7") (pinfunction "R2IN_7") (pintype "passive"))
    )
    (net (code "64") (name "/SHUT1_B") (class "Default")
      (node (ref "P1") (pin "23") (pinfunction "23_23") (pintype "passive"))
    )
    (net (code "65") (name "/SHUT2_B") (class "Default")
      (node (ref "P1") (pin "26") (pinfunction "26_26") (pintype "passive"))
    )
    (net (code "66") (name "/SHUT3_B") (class "Default")
      (node (ref "P1") (pin "27") (pinfunction "27_27") (pintype "passive"))
    )
    (net (code "67") (name "/SHUT4_B") (class "Default")
      (node (ref "P1") (pin "30") (pinfunction "30_30") (pintype "passive"))
    )
    (net (code "68") (name "/SI2C_SCL") (class "Default")
      (node (ref "P2") (pin "16") (pinfunction "16_16") (pintype "passive"))
      (node (ref "R11") (pin "1") (pinfunction "1_1") (pintype "passive"))
      (node (ref "U3") (pin "6") (pinfunction "SCL_6") (pintype "input"))
    )
    (net (code "69") (name "/SI2C_SDA") (class "Default")
      (node (ref "P2") (pin "13") (pinfunction "13_13") (pintype "passive"))
      (node (ref "R10") (pin "1") (pinfunction "1_1") (pintype "passive"))
      (node (ref "U3") (pin "5") (pinfunction "SDA_5") (pintype "bidirectional"))
    )
    (net (code "70") (name "/TIM8_BKIN") (class "Default")
      (node (ref "P2") (pin "58") (pinfunction "58_58") (pintype "passive"))
    )
    (net (code "71") (name "/TIM8_CH1N") (class "Default")
      (node (ref "P2") (pin "55") (pinfunction "55_55") (pintype "passive"))
    )
    (net (code "72") (name "/TXD1") (class "Default")
      (node (ref "P3") (pin "6") (pinfunction "6_6") (pintype "passive"))
      (node (ref "U2") (pin "10") (pinfunction "T1OUT_10") (pintype "passive"))
    )
    (net (code "73") (name "/TXD3") (class "Default")
      (node (ref "P3") (pin "4") (pinfunction "4_4") (pintype "passive"))
      (node (ref "U2") (pin "8") (pinfunction "T2OUT_8") (pintype "passive"))
    )
    (net (code "74") (name "/USART1_RX") (class "Default")
      (node (ref "P1") (pin "25") (pinfunction "25_25") (pintype "passive"))
      (node (ref "U2") (pin "4") (pinfunction "RXD1_4") (pintype "passive"))
    )
    (net (code "75") (name "/USART1_TX") (class "Default")
      (node (ref "P1") (pin "24") (pinfunction "24_24") (pintype "passive"))
      (node (ref "U2") (pin "3") (pinfunction "TXD1_3") (pintype "passive"))
    )
    (net (code "76") (name "/USART3_RX") (class "Default")
      (node (ref "P2") (pin "34") (pinfunction "34_34") (pintype "passive"))
      (node (ref "U2") (pin "6") (pinfunction "RXD2_6") (pintype "passive"))
    )
    (net (code "77") (name "/USART3_TX") (class "Default")
      (node (ref "P2") (pin "33") (pinfunction "33_33") (pintype "passive"))
      (node (ref "U2") (pin "5") (pinfunction "TXD2_5") (pintype "passive"))
    )
    (net (code "78") (name "/VBAT") (class "Default")
      (node (ref "P1") (pin "35") (pinfunction "35_35") (pintype "passive"))
    )
    (net (code "79") (name "/VDDA") (class "Default")
      (node (ref "P1") (pin "57") (pinfunction "57_57") (pintype "passive"))
    )
    (net (code "80") (name "/VREF") (class "Default")
      (node (ref "P1") (pin "56") (pinfunction "56_56") (pintype "passive"))
    )
    (net (code "81") (name "/X0") (class "Default")
      (node (ref "P3") (pin "12") (pinfunction "12_12") (pintype "passive"))
      (node (ref "R7") (pin "1") (pinfunction "1_1") (pintype "passive"))
    )
    (net (code "82") (name "/X1") (class "Default")
      (node (ref "P3") (pin "11") (pinfunction "11_11") (pintype "passive"))
      (node (ref "R5") (pin "1") (pinfunction "1_1") (pintype "passive"))
    )
    (net (code "83") (name "/Y0") (class "Default")
      (node (ref "OP1") (pin "4") (pinfunction "4_4") (pintype "passive"))
      (node (ref "OP1") (pin "6") (pinfunction "6_6") (pintype "passive"))
      (node (ref "P3") (pin "10") (pinfunction "10_10") (pintype "passive"))
    )
    (net (code "84") (name "/Y1") (class "Default")
      (node (ref "OP2") (pin "4") (pinfunction "4_4") (pintype "passive"))
      (node (ref "OP2") (pin "6") (pinfunction "6_6") (pintype "passive"))
      (node (ref "P3") (pin "9") (pinfunction "9_9") (pintype "passive"))
    )
    (net (code "85") (name "GND") (class "Default")
      (node (ref "C1") (pin "2") (pinfunction "2_2") (pintype "passive"))
      (node (ref "C10") (pin "1") (pinfunction "1_1") (pintype "passive"))
      (node (ref "C11") (pin "1") (pinfunction "1_1") (pintype "passive"))
      (node (ref "C12") (pin "1") (pinfunction "1_1") (pintype "passive"))
      (node (ref "C13") (pin "2") (pinfunction "2_2") (pintype "passive"))
      (node (ref "C14") (pin "1") (pinfunction "1_1") (pintype "passive"))
      (node (ref "C15") (pin "1") (pinfunction "1_1") (pintype "passive"))
      (node (ref "C16") (pin "2") (pinfunction "2_2") (pintype "passive"))
      (node (ref "C2") (pin "2") (pinfunction "2_2") (pintype "passive"))
      (node (ref "C3") (pin "1") (pinfunction "1_1") (pintype "passive"))
      (node (ref "C4") (pin "1") (pinfunction "1_1") (pintype "passive"))
      (node (ref "C5") (pin "1") (pinfunction "1_1") (pintype "passive"))
      (node (ref "C6") (pin "1") (pinfunction "1_1") (pintype "passive"))
      (node (ref "C7") (pin "1") (pinfunction "1_1") (pintype "passive"))
      (node (ref "C8") (pin "1") (pinfunction "1_1") (pintype "passive"))
      (node (ref "C9") (pin "1") (pinfunction "1_1") (pintype "passive"))
      (node (ref "D1") (pin "2") (pinfunction "K_2") (pintype "passive"))
      (node (ref "D10") (pin "2") (pinfunction "K_2") (pintype "passive"))
      (node (ref "D12") (pin "2") (pinfunction "K_2") (pintype "passive"))
      (node (ref "D3") (pin "2") (pinfunction "K_2") (pintype "passive"))
      (node (ref "D4") (pin "2") (pinfunction "K_2") (pintype "passive"))
      (node (ref "D5") (pin "2") (pinfunction "K_2") (pintype "passive"))
      (node (ref "D6") (pin "2") (pinfunction "K_2") (pintype "passive"))
      (node (ref "D7") (pin "2") (pinfunction "K_2") (pintype "passive"))
      (node (ref "D8") (pin "2") (pinfunction "K_2") (pintype "passive"))
      (node (ref "D9") (pin "2") (pinfunction "K_2") (pintype "passive"))
      (node (ref "DC1") (pin "6") (pinfunction "-Vo_6") (pintype "passive"))
      (node (ref "O1") (pin "5") (pinfunction "Em2_5") (pintype "passive"))
      (node (ref "O1") (pin "7") (pinfunction "Em1_7") (pintype "passive"))
      (node (ref "OP1") (pin "2") (pinfunction "2_2") (pintype "passive"))
      (node (ref "OP2") (pin "2") (pinfunction "2_2") (pintype "passive"))
      (node (ref "P1") (pin "55") (pinfunction "55_55") (pintype "passive"))
      (node (ref "P2") (pin "4") (pinfunction "4_4") (pintype "passive"))
      (node (ref "P4") (pin "10") (pinfunction "10_10") (pintype "passive"))
      (node (ref "P4") (pin "11") (pinfunction "11_11") (pintype "passive"))
      (node (ref "P4") (pin "9") (pinfunction "9_9") (pintype "passive"))
      (node (ref "P5") (pin "10") (pinfunction "10_10") (pintype "passive"))
      (node (ref "P5") (pin "11") (pinfunction "11_11") (pintype "passive"))
      (node (ref "P5") (pin "9") (pinfunction "9_9") (pintype "passive"))
      (node (ref "Q1") (pin "2") (pinfunction "E_2") (pintype "passive"))
      (node (ref "R17") (pin "2") (pinfunction "2_2") (pintype "passive"))
      (node (ref "R21") (pin "2") (pinfunction "2_2") (pintype "passive"))
      (node (ref "U1") (pin "12") (pinfunction "~{OE}_12") (pintype "input"))
      (node (ref "U1") (pin "8") (pinfunction "GND_8") (pintype "power_in"))
      (node (ref "U2") (pin "2") (pinfunction "GND_2") (pintype "passive"))
      (node (ref "U3") (pin "1") (pinfunction "E0_1") (pintype "input"))
      (node (ref "U3") (pin "2") (pinfunction "E1_2") (pintype "input"))
      (node (ref "U3") (pin "3") (pinfunction "E2_3") (pintype "input"))
      (node (ref "U3") (pin "4") (pinfunction "GND_4") (pintype "power_in"))
      (node (ref "U4") (pin "1") (pinfunction "IN_A_1") (pintype "input"))
      (node (ref "U4") (pin "12") (pinfunction "~{OE}_12") (pintype "input"))
      (node (ref "U4") (pin "7") (pinfunction "IN_B_7") (pintype "input"))
      (node (ref "U4") (pin "8") (pinfunction "GND_8") (pintype "power_in"))
      (node (ref "U5") (pin "12") (pinfunction "~{OE}_12") (pintype "input"))
      (node (ref "U5") (pin "7") (pinfunction "IN_C-_7") (pintype "input"))
      (node (ref "U5") (pin "8") (pinfunction "GND_8") (pintype "power_in"))
      (node (ref "U5") (pin "9") (pinfunction "IN_D-_9") (pintype "input"))
      (node (ref "U6") (pin "4") (pinfunction "V-_4") (pintype "power_in"))
      (node (ref "U7") (pin "7") (pinfunction "GND_7") (pintype "power_in"))
      (node (ref "U8") (pin "1") (pinfunction "GND_1") (pintype "power_in"))
    )
    (net (code "86") (name "GND24") (class "Default")
      (node (ref "C17") (pin "2") (pinfunction "2_2") (pintype "passive"))
      (node (ref "D13") (pin "1") (pinfunction "A_1") (pintype "passive"))
      (node (ref "DC1") (pin "2") (pinfunction "GND_2") (pintype "passive"))
      (node (ref "P3") (pin "1") (pinfunction "1_1") (pintype "passive"))
    )
    (net (code "87") (name "Net-(D1-A)") (class "Default")
      (node (ref "D1") (pin "1") (pinfunction "A_1") (pintype "passive"))
      (node (ref "R25") (pin "2") (pinfunction "2_2") (pintype "passive"))
    )
    (net (code "88") (name "Net-(D2-A)") (class "Default")
      (node (ref "D2") (pin "1") (pinfunction "A_1") (pintype "passive"))
      (node (ref "JQ1") (pin "8") (pinfunction "8_8") (pintype "passive"))
      (node (ref "Q1") (pin "3") (pinfunction "C_3") (pintype "passive"))
    )
    (net (code "89") (name "Net-(D3-A)") (class "Default")
      (node (ref "D3") (pin "1") (pinfunction "A_1") (pintype "passive"))
      (node (ref "R27") (pin "2") (pinfunction "2_2") (pintype "passive"))
    )
    (net (code "90") (name "Net-(D4-A)") (class "Default")
      (node (ref "D4") (pin "1") (pinfunction "A_1") (pintype "passive"))
      (node (ref "R28") (pin "2") (pinfunction "2_2") (pintype "passive"))
    )
    (net (code "91") (name "Net-(D5-A)") (class "Default")
      (node (ref "D5") (pin "1") (pinfunction "A_1") (pintype "passive"))
      (node (ref "R29") (pin "2") (pinfunction "2_2") (pintype "passive"))
    )
    (net (code "92") (name "Net-(D6-A)") (class "Default")
      (node (ref "D6") (pin "1") (pinfunction "A_1") (pintype "passive"))
      (node (ref "R30") (pin "2") (pinfunction "2_2") (pintype "passive"))
    )
    (net (code "93") (name "Net-(D7-A)") (class "Default")
      (node (ref "D7") (pin "1") (pinfunction "A_1") (pintype "passive"))
      (node (ref "R31") (pin "2") (pinfunction "2_2") (pintype "passive"))
    )
    (net (code "94") (name "Net-(D8-A)") (class "Default")
      (node (ref "D8") (pin "1") (pinfunction "A_1") (pintype "passive"))
      (node (ref "R32") (pin "2") (pinfunction "2_2") (pintype "passive"))
    )
    (net (code "95") (name "Net-(D9-A)") (class "Default")
      (node (ref "D9") (pin "1") (pinfunction "A_1") (pintype "passive"))
      (node (ref "R33") (pin "2") (pinfunction "2_2") (pintype "passive"))
    )
    (net (code "96") (name "Net-(D10-A)") (class "Default")
      (node (ref "D10") (pin "1") (pinfunction "A_1") (pintype "passive"))
      (node (ref "R34") (pin "2") (pinfunction "2_2") (pintype "passive"))
    )
    (net (code "97") (name "Net-(D12-A)") (class "Default")
      (node (ref "D12") (pin "1") (pinfunction "A_1") (pintype "passive"))
      (node (ref "R35") (pin "2") (pinfunction "2_2") (pintype "passive"))
    )
    (net (code "98") (name "Net-(O1-C1)") (class "Default")
      (node (ref "O1") (pin "2") (pinfunction "C1_2") (pintype "passive"))
      (node (ref "R5") (pin "2") (pinfunction "2_2") (pintype "passive"))
    )
    (net (code "99") (name "Net-(O1-C2)") (class "Default")
      (node (ref "O1") (pin "4") (pinfunction "C2_4") (pintype "passive"))
      (node (ref "R7") (pin "2") (pinfunction "2_2") (pintype "passive"))
    )
    (net (code "100") (name "Net-(OP1-Pad1)") (class "Default")
      (node (ref "OP1") (pin "1") (pinfunction "1_1") (pintype "passive"))
      (node (ref "R14") (pin "1") (pinfunction "1_1") (pintype "passive"))
    )
    (net (code "101") (name "Net-(OP2-Pad1)") (class "Default")
      (node (ref "OP2") (pin "1") (pinfunction "1_1") (pintype "passive"))
      (node (ref "R15") (pin "1") (pinfunction "1_1") (pintype "passive"))
    )
    (net (code "102") (name "Net-(U6A-IN+)") (class "Default")
      (node (ref "C4") (pin "2") (pinfunction "2_2") (pintype "passive"))
      (node (ref "R16") (pin "1") (pinfunction "1_1") (pintype "passive"))
      (node (ref "R17") (pin "1") (pinfunction "1_1") (pintype "passive"))
      (node (ref "U6") (pin "3") (pinfunction "IN+_3") (pintype "input"))
    )
    (net (code "103") (name "Net-(U6B-IN+)") (class "Default")
      (node (ref "C12") (pin "2") (pinfunction "2_2") (pintype "passive"))
      (node (ref "R18") (pin "1") (pinfunction "1_1") (pintype "passive"))
      (node (ref "R21") (pin "1") (pinfunction "1_1") (pintype "passive"))
      (node (ref "U6") (pin "5") (pinfunction "IN+_5") (pintype "input"))
    )
    (net (code "104") (name "Net-(U7A-Y)") (class "Default")
      (node (ref "R19") (pin "1") (pinfunction "1_1") (pintype "passive"))
      (node (ref "U7") (pin "3") (pinfunction "Y_3") (pintype "output"))
    )
    (net (code "105") (name "Net-(U7B-Y)") (class "Default")
      (node (ref "R22") (pin "1") (pinfunction "1_1") (pintype "passive"))
      (node (ref "U7") (pin "6") (pinfunction "Y_6") (pintype "output"))
    )
    (net (code "106") (name "Net-(U7C-Y)") (class "Default")
      (node (ref "R23") (pin "1") (pinfunction "1_1") (pintype "passive"))
      (node (ref "U7") (pin "8") (pinfunction "Y_8") (pintype "output"))
    )
    (net (code "107") (name "Net-(U7D-Y)") (class "Default")
      (node (ref "R26") (pin "1") (pinfunction "1_1") (pintype "passive"))
      (node (ref "U7") (pin "11") (pinfunction "Y_11") (pintype "output"))
    )
    (net (code "108") (name "VIN") (class "Default")
      (node (ref "D11") (pin "1") (pinfunction "A_1") (pintype "passive"))
      (node (ref "P3") (pin "2") (pinfunction "2_2") (pintype "passive"))
    )
    (net (code "109") (name "unconnected-(DC1-0V-Pad5)") (class "Default")
      (node (ref "DC1") (pin "5") (pinfunction "0V_5") (pintype "passive+no_connect"))
    )
    (net (code "110") (name "unconnected-(DC1-CTRL-Pad1)") (class "Default")
      (node (ref "DC1") (pin "1") (pinfunction "CTRL_1") (pintype "passive+no_connect"))
    )
    (net (code "111") (name "unconnected-(OP1-Pad3)") (class "Default")
      (node (ref "OP1") (pin "3") (pinfunction "3_3") (pintype "passive+no_connect"))
    )
    (net (code "112") (name "unconnected-(OP2-Pad3)") (class "Default")
      (node (ref "OP2") (pin "3") (pinfunction "3_3") (pintype "passive"))
    )
    (net (code "113") (name "unconnected-(P1-Pad1)") (class "Default")
      (node (ref "P1") (pin "1") (pinfunction "1_1") (pintype "passive+no_connect"))
    )
    (net (code "114") (name "unconnected-(P1-Pad2)") (class "Default")
      (node (ref "P1") (pin "2") (pinfunction "2_2") (pintype "passive+no_connect"))
    )
    (net (code "115") (name "unconnected-(P1-Pad4)") (class "Default")
      (node (ref "P1") (pin "4") (pinfunction "4_4") (pintype "passive"))
    )
    (net (code "116") (name "unconnected-(P1-Pad5)") (class "Default")
      (node (ref "P1") (pin "5") (pinfunction "5_5") (pintype "passive"))
    )
    (net (code "117") (name "unconnected-(P1-Pad6)") (class "Default")
      (node (ref "P1") (pin "6") (pinfunction "6_6") (pintype "passive+no_connect"))
    )
    (net (code "118") (name "unconnected-(P1-Pad7)") (class "Default")
      (node (ref "P1") (pin "7") (pinfunction "7_7") (pintype "passive+no_connect"))
    )
    (net (code "119") (name "unconnected-(P1-Pad8)") (class "Default")
      (node (ref "P1") (pin "8") (pinfunction "8_8") (pintype "passive"))
    )
    (net (code "120") (name "unconnected-(P1-Pad9)") (class "Default")
      (node (ref "P1") (pin "9") (pinfunction "9_9") (pintype "passive"))
    )
    (net (code "121") (name "unconnected-(P1-Pad10)") (class "Default")
      (node (ref "P1") (pin "10") (pinfunction "10_10") (pintype "passive+no_connect"))
    )
    (net (code "122") (name "unconnected-(P1-Pad11)") (class "Default")
      (node (ref "P1") (pin "11") (pinfunction "11_11") (pintype "passive+no_connect"))
    )
    (net (code "123") (name "unconnected-(P1-Pad12)") (class "Default")
      (node (ref "P1") (pin "12") (pinfunction "12_12") (pintype "passive+no_connect"))
    )
    (net (code "124") (name "unconnected-(P1-Pad13)") (class "Default")
      (node (ref "P1") (pin "13") (pinfunction "13_13") (pintype "passive+no_connect"))
    )
    (net (code "125") (name "unconnected-(P1-Pad14)") (class "Default")
      (node (ref "P1") (pin "14") (pinfunction "14_14") (pintype "passive+no_connect"))
    )
    (net (code "126") (name "unconnected-(P1-Pad15)") (class "Default")
      (node (ref "P1") (pin "15") (pinfunction "15_15") (pintype "passive+no_connect"))
    )
    (net (code "127") (name "unconnected-(P1-Pad17)") (class "Default")
      (node (ref "P1") (pin "17") (pinfunction "17_17") (pintype "passive+no_connect"))
    )
    (net (code "128") (name "unconnected-(P1-Pad21)") (class "Default")
      (node (ref "P1") (pin "21") (pinfunction "21_21") (pintype "passive+no_connect"))
    )
    (net (code "129") (name "unconnected-(P1-Pad22)") (class "Default")
      (node (ref "P1") (pin "22") (pinfunction "22_22") (pintype "passive+no_connect"))
    )
    (net (code "130") (name "unconnected-(P1-Pad28)") (class "Default")
      (node (ref "P1") (pin "28") (pinfunction "28_28") (pintype "passive+no_connect"))
    )
    (net (code "131") (name "unconnected-(P1-Pad29)") (class "Default")
      (node (ref "P1") (pin "29") (pinfunction "29_29") (pintype "passive+no_connect"))
    )
    (net (code "132") (name "unconnected-(P1-Pad31)") (class "Default")
      (node (ref "P1") (pin "31") (pinfunction "31_31") (pintype "passive+no_connect"))
    )
    (net (code "133") (name "unconnected-(P1-Pad32)") (class "Default")
      (node (ref "P1") (pin "32") (pinfunction "32_32") (pintype "passive+no_connect"))
    )
    (net (code "134") (name "unconnected-(P1-Pad33)") (class "Default")
      (node (ref "P1") (pin "33") (pinfunction "33_33") (pintype "passive+no_connect"))
    )
    (net (code "135") (name "unconnected-(P1-Pad34)") (class "Default")
      (node (ref "P1") (pin "34") (pinfunction "34_34") (pintype "passive+no_connect"))
    )
    (net (code "136") (name "unconnected-(P1-Pad37)") (class "Default")
      (node (ref "P1") (pin "37") (pinfunction "37_37") (pintype "passive+no_connect"))
    )
    (net (code "137") (name "unconnected-(P1-Pad38)") (class "Default")
      (node (ref "P1") (pin "38") (pinfunction "38_38") (pintype "passive+no_connect"))
    )
    (net (code "138") (name "unconnected-(P1-Pad39)") (class "Default")
      (node (ref "P1") (pin "39") (pinfunction "39_39") (pintype "passive+no_connect"))
    )
    (net (code "139") (name "unconnected-(P1-Pad40)") (class "Default")
      (node (ref "P1") (pin "40") (pinfunction "40_40") (pintype "passive+no_connect"))
    )
    (net (code "140") (name "unconnected-(P1-Pad41)") (class "Default")
      (node (ref "P1") (pin "41") (pinfunction "41_41") (pintype "passive+no_connect"))
    )
    (net (code "141") (name "unconnected-(P1-Pad42)") (class "Default")
      (node (ref "P1") (pin "42") (pinfunction "42_42") (pintype "passive+no_connect"))
    )
    (net (code "142") (name "unconnected-(P1-Pad43)") (class "Default")
      (node (ref "P1") (pin "43") (pinfunction "43_43") (pintype "passive+no_connect"))
    )
    (net (code "143") (name "unconnected-(P1-Pad44)") (class "Default")
      (node (ref "P1") (pin "44") (pinfunction "44_44") (pintype "passive+no_connect"))
    )
    (net (code "144") (name "unconnected-(P1-Pad45)") (class "Default")
      (node (ref "P1") (pin "45") (pinfunction "45_45") (pintype "passive"))
    )
    (net (code "145") (name "unconnected-(P1-Pad46)") (class "Default")
      (node (ref "P1") (pin "46") (pinfunction "46_46") (pintype "passive"))
    )
    (net (code "146") (name "unconnected-(P1-Pad48)") (class "Default")
      (node (ref "P1") (pin "48") (pinfunction "48_48") (pintype "passive"))
    )
    (net (code "147") (name "unconnected-(P1-Pad49)") (class "Default")
      (node (ref "P1") (pin "49") (pinfunction "49_49") (pintype "passive"))
    )
    (net (code "148") (name "unconnected-(P1-Pad52)") (class "Default")
      (node (ref "P1") (pin "52") (pinfunction "52_52") (pintype "passive"))
    )
    (net (code "149") (name "unconnected-(P1-Pad53)") (class "Default")
      (node (ref "P1") (pin "53") (pinfunction "53_53") (pintype "passive"))
    )
    (net (code "150") (name "unconnected-(P2-Pad2)") (class "Default")
      (node (ref "P2") (pin "2") (pinfunction "2_2") (pintype "passive+no_connect"))
    )
    (net (code "151") (name "unconnected-(P2-Pad15)") (class "Default")
      (node (ref "P2") (pin "15") (pinfunction "15_15") (pintype "passive+no_connect"))
    )
    (net (code "152") (name "unconnected-(P2-Pad17)") (class "Default")
      (node (ref "P2") (pin "17") (pinfunction "17_17") (pintype "passive+no_connect"))
    )
    (net (code "153") (name "unconnected-(P2-Pad18)") (class "Default")
      (node (ref "P2") (pin "18") (pinfunction "18_18") (pintype "passive+no_connect"))
    )
    (net (code "154") (name "unconnected-(P2-Pad19)") (class "Default")
      (node (ref "P2") (pin "19") (pinfunction "19_19") (pintype "passive+no_connect"))
    )
    (net (code "155") (name "unconnected-(P2-Pad20)") (class "Default")
      (node (ref "P2") (pin "20") (pinfunction "20_20") (pintype "passive+no_connect"))
    )
    (net (code "156") (name "unconnected-(P2-Pad21)") (class "Default")
      (node (ref "P2") (pin "21") (pinfunction "21_21") (pintype "passive+no_connect"))
    )
    (net (code "157") (name "unconnected-(P2-Pad22)") (class "Default")
      (node (ref "P2") (pin "22") (pinfunction "22_22") (pintype "passive+no_connect"))
    )
    (net (code "158") (name "unconnected-(P2-Pad23)") (class "Default")
      (node (ref "P2") (pin "23") (pinfunction "23_23") (pintype "passive+no_connect"))
    )
    (net (code "159") (name "unconnected-(P2-Pad24)") (class "Default")
      (node (ref "P2") (pin "24") (pinfunction "24_24") (pintype "passive+no_connect"))
    )
    (net (code "160") (name "unconnected-(P2-Pad25)") (class "Default")
      (node (ref "P2") (pin "25") (pinfunction "25_25") (pintype "passive+no_connect"))
    )
    (net (code "161") (name "unconnected-(P2-Pad26)") (class "Default")
      (node (ref "P2") (pin "26") (pinfunction "26_26") (pintype "passive+no_connect"))
    )
    (net (code "162") (name "unconnected-(P2-Pad27)") (class "Default")
      (node (ref "P2") (pin "27") (pinfunction "27_27") (pintype "passive+no_connect"))
    )
    (net (code "163") (name "unconnected-(P2-Pad28)") (class "Default")
      (node (ref "P2") (pin "28") (pinfunction "28_28") (pintype "passive+no_connect"))
    )
    (net (code "164") (name "unconnected-(P2-Pad35)") (class "Default")
      (node (ref "P2") (pin "35") (pinfunction "35_35") (pintype "passive+no_connect"))
    )
    (net (code "165") (name "unconnected-(P2-Pad36)") (class "Default")
      (node (ref "P2") (pin "36") (pinfunction "36_36") (pintype "passive+no_connect"))
    )
    (net (code "166") (name "unconnected-(P2-Pad37)") (class "Default")
      (node (ref "P2") (pin "37") (pinfunction "37_37") (pintype "passive"))
    )
    (net (code "167") (name "unconnected-(P2-Pad38)") (class "Default")
      (node (ref "P2") (pin "38") (pinfunction "38_38") (pintype "passive+no_connect"))
    )
    (net (code "168") (name "unconnected-(P2-Pad39)") (class "Default")
      (node (ref "P2") (pin "39") (pinfunction "39_39") (pintype "passive+no_connect"))
    )
    (net (code "169") (name "unconnected-(P2-Pad40)") (class "Default")
      (node (ref "P2") (pin "40") (pinfunction "40_40") (pintype "passive+no_connect"))
    )
    (net (code "170") (name "unconnected-(P2-Pad41)") (class "Default")
      (node (ref "P2") (pin "41") (pinfunction "41_41") (pintype "passive+no_connect"))
    )
    (net (code "171") (name "unconnected-(P2-Pad42)") (class "Default")
      (node (ref "P2") (pin "42") (pinfunction "42_42") (pintype "passive+no_connect"))
    )
    (net (code "172") (name "unconnected-(P2-Pad43)") (class "Default")
      (node (ref "P2") (pin "43") (pinfunction "43_43") (pintype "passive+no_connect"))
    )
    (net (code "173") (name "unconnected-(P2-Pad44)") (class "Default")
      (node (ref "P2") (pin "44") (pinfunction "44_44") (pintype "passive+no_connect"))
    )
    (net (code "174") (name "unconnected-(P2-Pad45)") (class "Default")
      (node (ref "P2") (pin "45") (pinfunction "45_45") (pintype "passive+no_connect"))
    )
    (net (code "175") (name "unconnected-(P2-Pad46)") (class "Default")
      (node (ref "P2") (pin "46") (pinfunction "46_46") (pintype "passive+no_connect"))
    )
    (net (code "176") (name "unconnected-(P2-Pad47)") (class "Default")
      (node (ref "P2") (pin "47") (pinfunction "47_47") (pintype "passive+no_connect"))
    )
    (net (code "177") (name "unconnected-(P2-Pad48)") (class "Default")
      (node (ref "P2") (pin "48") (pinfunction "48_48") (pintype "passive+no_connect"))
    )
    (net (code "178") (name "unconnected-(P2-Pad50)") (class "Default")
      (node (ref "P2") (pin "50") (pinfunction "50_50") (pintype "passive+no_connect"))
    )
    (net (code "179") (name "unconnected-(U3-~{WC}-Pad7)") (class "Default")
      (node (ref "U3") (pin "7") (pinfunction "~{WC}_7") (pintype "input+no_connect"))
    )
    (net (code "180") (name "unconnected-(U4-IN_D-Pad15)") (class "Default")
      (node (ref "U4") (pin "15") (pinfunction "IN_D_15") (pintype "input+no_connect"))
    )
    (net (code "181") (name "unconnected-(U4-OUT_A-Pad2)") (class "Default")
      (node (ref "U4") (pin "2") (pinfunction "OUT_A_2") (pintype "tri_state+no_connect"))
    )
    (net (code "182") (name "unconnected-(U4-OUT_B-Pad6)") (class "Default")
      (node (ref "U4") (pin "6") (pinfunction "OUT_B_6") (pintype "tri_state+no_connect"))
    )
    (net (code "183") (name "unconnected-(U4-OUT_D-Pad14)") (class "Default")
      (node (ref "U4") (pin "14") (pinfunction "OUT_D_14") (pintype "tri_state+no_connect"))
    )
    (net (code "184") (name "unconnected-(U4-~{OUT}_A-Pad3)") (class "Default")
      (node (ref "U4") (pin "3") (pinfunction "~{OUT}_A_3") (pintype "tri_state+no_connect"))
    )
    (net (code "185") (name "unconnected-(U4-~{OUT}_B-Pad5)") (class "Default")
      (node (ref "U4") (pin "5") (pinfunction "~{OUT}_B_5") (pintype "tri_state+no_connect"))
    )
    (net (code "186") (name "unconnected-(U4-~{OUT}_D-Pad13)") (class "Default")
      (node (ref "U4") (pin "13") (pinfunction "~{OUT}_D_13") (pintype "tri_state+no_connect"))
    )
    (net (code "187") (name "unconnected-(U5-OUT_C-Pad5)") (class "Default")
      (node (ref "U5") (pin "5") (pinfunction "OUT_C_5") (pintype "tri_state+no_connect"))
    )
    (net (code "188") (name "unconnected-(U5-OUT_D-Pad11)") (class "Default")
      (node (ref "U5") (pin "11") (pinfunction "OUT_D_11") (pintype "tri_state+no_connect"))
    )
  )
)
